# blue_lora_v2.net
KiCad netlist of a schematic drawn in EAGLE
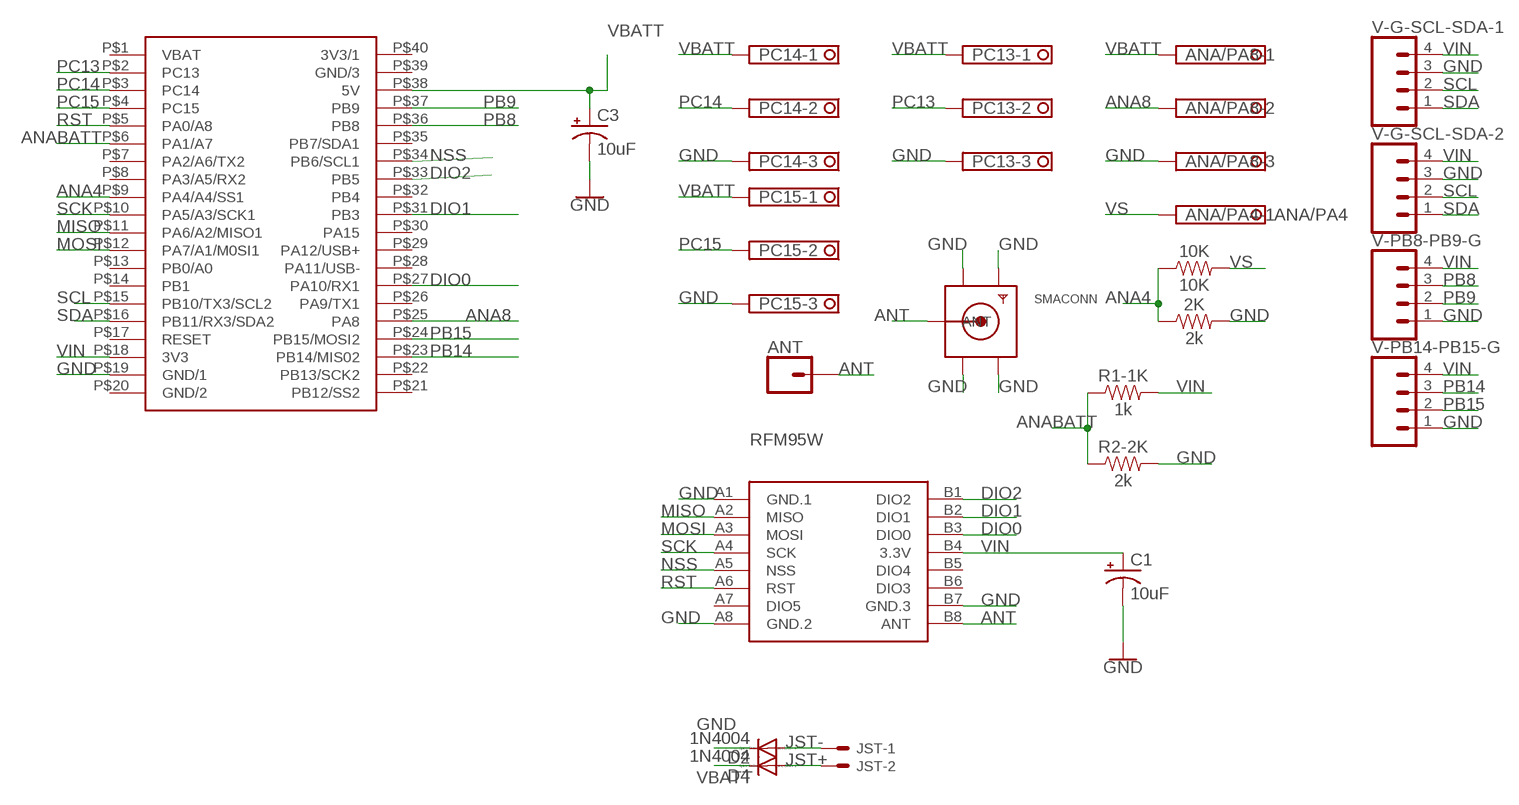
[diagram p0: schematic, sheet 1]

(export (version "E")
  (design (tool "Eeschema 10.0.6"))
  (components
    (comp (ref "2K")
      (value "2k")
      (footprint "eagle-import:AXIAL-0.3-KIT")
      (libsource (lib "eagle-import") (part "1KOHM-HORIZ_KIT-1/4W-1%"))
    )
    (comp (ref "10K")
      (value "10K")
      (footprint "eagle-import:AXIAL-0.3-KIT")
      (libsource (lib "eagle-import") (part "1KOHM-HORIZ_KIT-1/4W-1%"))
    )
    (comp (ref "ANA/PA4")
      (value "ANA/PA4")
      (footprint "eagle-import:TERMINAL-BLOCK-2-PIN-3.5MM-LONG-PAD")
      (libsource (lib "eagle-import") (part "TERMINAL-BLOCK-3.5MM-2-PIN-LONG-PAD"))
    )
    (comp (ref "ANA/PA8")
      (value "TERMINAL-BLOCK-3.5MM-3-PIN-LONG-PAD")
      (footprint "eagle-import:TERMINAL-BLOCK-3-PIN-3.5MM-LONG-PAD")
      (libsource (lib "eagle-import") (part "TERMINAL-BLOCK-3.5MM-3-PIN-LONG-PAD"))
    )
    (comp (ref "ANT")
      (value "CONN_01")
      (footprint "eagle-import:1X01")
      (libsource (lib "eagle-import") (part "CONN_01"))
    )
    (comp (ref "C1")
      (value "10uF")
      (footprint "eagle-import:CPOL-RADIAL-2.5MM-5MM")
      (libsource (lib "eagle-import") (part "10UF-POLAR-RADIAL-2.5MM-25V-20%"))
    )
    (comp (ref "C3")
      (value "10uF")
      (footprint "eagle-import:CPOL-RADIAL-2.5MM-5MM")
      (libsource (lib "eagle-import") (part "10UF-POLAR-RADIAL-2.5MM-25V-20%"))
    )
    (comp (ref "D2")
      (value "1N4004")
      (footprint "eagle-import:DO41-10")
      (libsource (lib "eagle-import") (part "1N4004"))
    )
    (comp (ref "D4")
      (value "1N4004")
      (footprint "eagle-import:DO41-10")
      (libsource (lib "eagle-import") (part "1N4004"))
    )
    (comp (ref "JST")
      (value "JST-XH-02-PIN-LONG-PAD")
      (footprint "eagle-import:JST-XH-02-PACKAGE-LONG-PAD")
      (libsource (lib "eagle-import") (part "JST-XH-02-PIN-LONG-PAD"))
    )
    (comp (ref "PC13")
      (value "TERMINAL-BLOCK-3.5MM-3-PIN-LONG-PAD")
      (footprint "eagle-import:TERMINAL-BLOCK-3-PIN-3.5MM-LONG-PAD")
      (libsource (lib "eagle-import") (part "TERMINAL-BLOCK-3.5MM-3-PIN-LONG-PAD"))
    )
    (comp (ref "PC14")
      (value "TERMINAL-BLOCK-3.5MM-3-PIN-LONG-PAD")
      (footprint "eagle-import:TERMINAL-BLOCK-3-PIN-3.5MM-LONG-PAD")
      (libsource (lib "eagle-import") (part "TERMINAL-BLOCK-3.5MM-3-PIN-LONG-PAD"))
    )
    (comp (ref "PC15")
      (value "TERMINAL-BLOCK-3.5MM-3-PIN-LONG-PAD")
      (footprint "eagle-import:TERMINAL-BLOCK-3-PIN-3.5MM-LONG-PAD")
      (libsource (lib "eagle-import") (part "TERMINAL-BLOCK-3.5MM-3-PIN-LONG-PAD"))
    )
    (comp (ref "R1-1K")
      (value "1k")
      (footprint "eagle-import:AXIAL-0.3-KIT")
      (libsource (lib "eagle-import") (part "1KOHM-HORIZ_KIT-1/4W-1%"))
    )
    (comp (ref "R2-2K")
      (value "2k")
      (footprint "eagle-import:AXIAL-0.3-KIT")
      (libsource (lib "eagle-import") (part "1KOHM-HORIZ_KIT-1/4W-1%"))
    )
    (comp (ref "RFM95W")
      (value "WIRELESS-LORA-RFM95W#SMD")
      (footprint "eagle-import:WIRELESS-LORA-RFM95W#SMD")
      (libsource (lib "eagle-import") (part "WIRELESS-LORA-RFM95W#SMD"))
    )
    (comp (ref "SMACONN")
      (value "SMACONNECTOR_EDGE")
      (footprint "eagle-import:SMA_EDGELAUNCH")
      (libsource (lib "eagle-import") (part "SMACONNECTOR_EDGE"))
    )
    (comp (ref "U$2")
      (value "BLUEPILL")
      (footprint "eagle-import:BLUEPILL")
      (libsource (lib "eagle-import") (part "BLUEPILL"))
    )
    (comp (ref "V-G-SCL-SDA-1")
      (value "CONN_04LOCK_LONGPADS")
      (footprint "eagle-import:1X04_LOCK_LONGPADS")
      (libsource (lib "eagle-import") (part "CONN_04LOCK_LONGPADS"))
    )
    (comp (ref "V-G-SCL-SDA-2")
      (value "CONN_04LOCK_LONGPADS")
      (footprint "eagle-import:1X04_LOCK_LONGPADS")
      (libsource (lib "eagle-import") (part "CONN_04LOCK_LONGPADS"))
    )
    (comp (ref "V-PB8-PB9-G")
      (value "CONN_04LOCK_LONGPADS")
      (footprint "eagle-import:1X04_LOCK_LONGPADS")
      (libsource (lib "eagle-import") (part "CONN_04LOCK_LONGPADS"))
    )
    (comp (ref "V-PB14-PB15-G")
      (value "CONN_04LOCK_LONGPADS")
      (footprint "eagle-import:1X04_LOCK_LONGPADS")
      (libsource (lib "eagle-import") (part "CONN_04LOCK_LONGPADS"))
    )
  )
  (nets
    (net (code "1") (name "/ANA4") (class "Default")
      (node (ref "10K") (pin "P$1") (pinfunction "1_P$1") (pintype "passive"))
      (node (ref "2K") (pin "P$1") (pinfunction "1_P$1") (pintype "passive"))
      (node (ref "U$2") (pin "P$9") (pinfunction "PA4/A4/SS1_P$9") (pintype "bidirectional"))
    )
    (net (code "2") (name "/ANA8") (class "Default")
      (node (ref "ANA/PA8") (pin "2") (pinfunction "K_2") (pintype "passive"))
      (node (ref "U$2") (pin "P$25") (pinfunction "PA8_P$25") (pintype "bidirectional"))
    )
    (net (code "3") (name "/ANABATT") (class "Default")
      (node (ref "R1-1K") (pin "P$1") (pinfunction "1_P$1") (pintype "passive"))
      (node (ref "R2-2K") (pin "P$1") (pinfunction "1_P$1") (pintype "passive"))
      (node (ref "U$2") (pin "P$6") (pinfunction "PA1/A7_P$6") (pintype "bidirectional"))
    )
    (net (code "4") (name "/ANT") (class "Default")
      (node (ref "ANT") (pin "1") (pinfunction "1_1") (pintype "passive"))
      (node (ref "RFM95W") (pin "B8") (pinfunction "ANT_B8") (pintype "passive"))
      (node (ref "SMACONN") (pin "P") (pinfunction "ANT_P") (pintype "bidirectional"))
    )
    (net (code "5") (name "/DIO0") (class "Default")
      (node (ref "RFM95W") (pin "B3") (pinfunction "DIO0_B3") (pintype "bidirectional"))
      (node (ref "U$2") (pin "P$27") (pinfunction "PA10/RX1_P$27") (pintype "bidirectional"))
    )
    (net (code "6") (name "/DIO1") (class "Default")
      (node (ref "RFM95W") (pin "B2") (pinfunction "DIO1_B2") (pintype "bidirectional"))
      (node (ref "U$2") (pin "P$31") (pinfunction "PB3_P$31") (pintype "bidirectional"))
    )
    (net (code "7") (name "/DIO2") (class "Default")
      (node (ref "RFM95W") (pin "B1") (pinfunction "DIO2_B1") (pintype "bidirectional"))
      (node (ref "U$2") (pin "P$33") (pinfunction "PB5_P$33") (pintype "bidirectional"))
    )
    (net (code "8") (name "/JST+") (class "Default")
      (node (ref "D4") (pin "A") (pinfunction "A_A") (pintype "passive"))
      (node (ref "JST") (pin "2") (pinfunction "S_2") (pintype "passive"))
    )
    (net (code "9") (name "/JST-") (class "Default")
      (node (ref "D2") (pin "A") (pinfunction "A_A") (pintype "passive"))
      (node (ref "JST") (pin "1") (pinfunction "S_1") (pintype "passive"))
    )
    (net (code "10") (name "/MISO") (class "Default")
      (node (ref "RFM95W") (pin "A2") (pinfunction "MISO_A2") (pintype "bidirectional"))
      (node (ref "U$2") (pin "P$11") (pinfunction "PA6/A2/MISO1_P$11") (pintype "bidirectional"))
    )
    (net (code "11") (name "/MOSI") (class "Default")
      (node (ref "RFM95W") (pin "A3") (pinfunction "MOSI_A3") (pintype "bidirectional"))
      (node (ref "U$2") (pin "P$12") (pinfunction "PA7/A1/M0SI1_P$12") (pintype "bidirectional"))
    )
    (net (code "12") (name "/NSS") (class "Default")
      (node (ref "RFM95W") (pin "A5") (pinfunction "NSS_A5") (pintype "bidirectional"))
      (node (ref "U$2") (pin "P$34") (pinfunction "PB6/SCL1_P$34") (pintype "bidirectional"))
    )
    (net (code "13") (name "/PB8") (class "Default")
      (node (ref "U$2") (pin "P$36") (pinfunction "PB8_P$36") (pintype "bidirectional"))
      (node (ref "V-PB8-PB9-G") (pin "3") (pinfunction "3_3") (pintype "passive"))
    )
    (net (code "14") (name "/PB9") (class "Default")
      (node (ref "U$2") (pin "P$37") (pinfunction "PB9_P$37") (pintype "bidirectional"))
      (node (ref "V-PB8-PB9-G") (pin "2") (pinfunction "2_2") (pintype "passive"))
    )
    (net (code "15") (name "/PB14") (class "Default")
      (node (ref "U$2") (pin "P$23") (pinfunction "PB14/MIS02_P$23") (pintype "bidirectional"))
      (node (ref "V-PB14-PB15-G") (pin "3") (pinfunction "3_3") (pintype "passive"))
    )
    (net (code "16") (name "/PB15") (class "Default")
      (node (ref "U$2") (pin "P$24") (pinfunction "PB15/MOSI2_P$24") (pintype "bidirectional"))
      (node (ref "V-PB14-PB15-G") (pin "2") (pinfunction "2_2") (pintype "passive"))
    )
    (net (code "17") (name "/PC13") (class "Default")
      (node (ref "PC13") (pin "2") (pinfunction "K_2") (pintype "passive"))
      (node (ref "U$2") (pin "P$2") (pinfunction "PC13_P$2") (pintype "bidirectional"))
    )
    (net (code "18") (name "/PC14") (class "Default")
      (node (ref "PC14") (pin "2") (pinfunction "K_2") (pintype "passive"))
      (node (ref "U$2") (pin "P$3") (pinfunction "PC14_P$3") (pintype "bidirectional"))
    )
    (net (code "19") (name "/PC15") (class "Default")
      (node (ref "PC15") (pin "2") (pinfunction "K_2") (pintype "passive"))
      (node (ref "U$2") (pin "P$4") (pinfunction "PC15_P$4") (pintype "bidirectional"))
    )
    (net (code "20") (name "/RST") (class "Default")
      (node (ref "RFM95W") (pin "A6") (pinfunction "RST_A6") (pintype "bidirectional"))
      (node (ref "U$2") (pin "P$5") (pinfunction "PA0/A8_P$5") (pintype "bidirectional"))
    )
    (net (code "21") (name "/SCK") (class "Default")
      (node (ref "RFM95W") (pin "A4") (pinfunction "SCK_A4") (pintype "bidirectional"))
      (node (ref "U$2") (pin "P$10") (pinfunction "PA5/A3/SCK1_P$10") (pintype "bidirectional"))
    )
    (net (code "22") (name "/SCL") (class "Default")
      (node (ref "U$2") (pin "P$15") (pinfunction "PB10/TX3/SCL2_P$15") (pintype "bidirectional"))
      (node (ref "V-G-SCL-SDA-1") (pin "2") (pinfunction "2_2") (pintype "passive"))
      (node (ref "V-G-SCL-SDA-2") (pin "2") (pinfunction "2_2") (pintype "passive"))
    )
    (net (code "23") (name "/SDA") (class "Default")
      (node (ref "U$2") (pin "P$16") (pinfunction "PB11/RX3/SDA2_P$16") (pintype "bidirectional"))
      (node (ref "V-G-SCL-SDA-1") (pin "1") (pinfunction "1_1") (pintype "passive"))
      (node (ref "V-G-SCL-SDA-2") (pin "1") (pinfunction "1_1") (pintype "passive"))
    )
    (net (code "24") (name "/VBATT") (class "Default")
      (node (ref "ANA/PA8") (pin "1") (pinfunction "K_1") (pintype "passive"))
      (node (ref "C3") (pin "1") (pinfunction "+_1") (pintype "passive"))
      (node (ref "D4") (pin "C") (pinfunction "C_C") (pintype "passive"))
      (node (ref "PC13") (pin "1") (pinfunction "K_1") (pintype "passive"))
      (node (ref "PC14") (pin "1") (pinfunction "K_1") (pintype "passive"))
      (node (ref "PC15") (pin "1") (pinfunction "K_1") (pintype "passive"))
      (node (ref "U$2") (pin "P$38") (pinfunction "5V_P$38") (pintype "bidirectional"))
    )
    (net (code "25") (name "/VIN") (class "Default")
      (node (ref "C1") (pin "1") (pinfunction "+_1") (pintype "passive"))
      (node (ref "R1-1K") (pin "P$2") (pinfunction "2_P$2") (pintype "passive"))
      (node (ref "RFM95W") (pin "B4") (pinfunction "3.3V_B4") (pintype "power_in"))
      (node (ref "U$2") (pin "P$18") (pinfunction "3V3_P$18") (pintype "bidirectional"))
      (node (ref "V-G-SCL-SDA-1") (pin "4") (pinfunction "4_4") (pintype "passive"))
      (node (ref "V-G-SCL-SDA-2") (pin "4") (pinfunction "4_4") (pintype "passive"))
      (node (ref "V-PB14-PB15-G") (pin "4") (pinfunction "4_4") (pintype "passive"))
      (node (ref "V-PB8-PB9-G") (pin "4") (pinfunction "4_4") (pintype "passive"))
    )
    (net (code "26") (name "/VS") (class "Default")
      (node (ref "10K") (pin "P$2") (pinfunction "2_P$2") (pintype "passive"))
      (node (ref "ANA/PA4") (pin "1") (pinfunction "K_1") (pintype "passive"))
    )
    (net (code "27") (name "GND") (class "Default")
      (node (ref "2K") (pin "P$2") (pinfunction "2_P$2") (pintype "passive"))
      (node (ref "ANA/PA8") (pin "3") (pinfunction "K_3") (pintype "passive"))
      (node (ref "C1") (pin "2") (pinfunction "-_2") (pintype "passive"))
      (node (ref "C3") (pin "2") (pinfunction "-_2") (pintype "passive"))
      (node (ref "D2") (pin "C") (pinfunction "C_C") (pintype "passive"))
      (node (ref "PC13") (pin "3") (pinfunction "K_3") (pintype "passive"))
      (node (ref "PC14") (pin "3") (pinfunction "K_3") (pintype "passive"))
      (node (ref "PC15") (pin "3") (pinfunction "K_3") (pintype "passive"))
      (node (ref "R2-2K") (pin "P$2") (pinfunction "2_P$2") (pintype "passive"))
      (node (ref "RFM95W") (pin "A1") (pinfunction "GND.1_A1") (pintype "power_in"))
      (node (ref "RFM95W") (pin "A8") (pinfunction "GND.2_A8") (pintype "power_in"))
      (node (ref "RFM95W") (pin "B7") (pinfunction "GND.3_B7") (pintype "power_in"))
      (node (ref "SMACONN") (pin "GND@1") (pinfunction "GND4_GND@1") (pintype "power_in"))
      (node (ref "SMACONN") (pin "GND@2") (pinfunction "GND3_GND@2") (pintype "power_in"))
      (node (ref "SMACONN") (pin "GND@3") (pinfunction "GND2_GND@3") (pintype "power_in"))
      (node (ref "SMACONN") (pin "GND@4") (pinfunction "GND1_GND@4") (pintype "power_in"))
      (node (ref "U$2") (pin "P$19") (pinfunction "GND/1_P$19") (pintype "bidirectional"))
      (node (ref "V-G-SCL-SDA-1") (pin "3") (pinfunction "3_3") (pintype "passive"))
      (node (ref "V-G-SCL-SDA-2") (pin "3") (pinfunction "3_3") (pintype "passive"))
      (node (ref "V-PB14-PB15-G") (pin "1") (pinfunction "1_1") (pintype "passive"))
      (node (ref "V-PB8-PB9-G") (pin "1") (pinfunction "1_1") (pintype "passive"))
    )
    (net (code "28") (name "unconnected-(RFM95W-DIO3-PadB6)") (class "Default")
      (node (ref "RFM95W") (pin "B6") (pinfunction "DIO3_B6") (pintype "bidirectional"))
    )
    (net (code "29") (name "unconnected-(RFM95W-DIO4-PadB5)") (class "Default")
      (node (ref "RFM95W") (pin "B5") (pinfunction "DIO4_B5") (pintype "bidirectional"))
    )
    (net (code "30") (name "unconnected-(RFM95W-DIO5-PadA7)") (class "Default")
      (node (ref "RFM95W") (pin "A7") (pinfunction "DIO5_A7") (pintype "bidirectional"))
    )
    (net (code "31") (name "unconnected-(U$2-3V3{slash}1-PadP$40)") (class "Default")
      (node (ref "U$2") (pin "P$40") (pinfunction "3V3/1_P$40") (pintype "bidirectional"))
    )
    (net (code "32") (name "unconnected-(U$2-GND{slash}2-PadP$20)") (class "Default")
      (node (ref "U$2") (pin "P$20") (pinfunction "GND/2_P$20") (pintype "bidirectional"))
    )
    (net (code "33") (name "unconnected-(U$2-GND{slash}3-PadP$39)") (class "Default")
      (node (ref "U$2") (pin "P$39") (pinfunction "GND/3_P$39") (pintype "bidirectional"))
    )
    (net (code "34") (name "unconnected-(U$2-PA2{slash}A6{slash}TX2-PadP$7)") (class "Default")
      (node (ref "U$2") (pin "P$7") (pinfunction "PA2/A6/TX2_P$7") (pintype "bidirectional"))
    )
    (net (code "35") (name "unconnected-(U$2-PA3{slash}A5{slash}RX2-PadP$8)") (class "Default")
      (node (ref "U$2") (pin "P$8") (pinfunction "PA3/A5/RX2_P$8") (pintype "bidirectional"))
    )
    (net (code "36") (name "unconnected-(U$2-PA9{slash}TX1-PadP$26)") (class "Default")
      (node (ref "U$2") (pin "P$26") (pinfunction "PA9/TX1_P$26") (pintype "bidirectional"))
    )
    (net (code "37") (name "unconnected-(U$2-PA11{slash}USB--PadP$28)") (class "Default")
      (node (ref "U$2") (pin "P$28") (pinfunction "PA11/USB-_P$28") (pintype "bidirectional"))
    )
    (net (code "38") (name "unconnected-(U$2-PA12{slash}USB+-PadP$29)") (class "Default")
      (node (ref "U$2") (pin "P$29") (pinfunction "PA12/USB+_P$29") (pintype "bidirectional"))
    )
    (net (code "39") (name "unconnected-(U$2-PA15-PadP$30)") (class "Default")
      (node (ref "U$2") (pin "P$30") (pinfunction "PA15_P$30") (pintype "bidirectional"))
    )
    (net (code "40") (name "unconnected-(U$2-PB0{slash}A0-PadP$13)") (class "Default")
      (node (ref "U$2") (pin "P$13") (pinfunction "PB0/A0_P$13") (pintype "bidirectional"))
    )
    (net (code "41") (name "unconnected-(U$2-PB1-PadP$14)") (class "Default")
      (node (ref "U$2") (pin "P$14") (pinfunction "PB1_P$14") (pintype "bidirectional"))
    )
    (net (code "42") (name "unconnected-(U$2-PB4-PadP$32)") (class "Default")
      (node (ref "U$2") (pin "P$32") (pinfunction "PB4_P$32") (pintype "bidirectional"))
    )
    (net (code "43") (name "unconnected-(U$2-PB7{slash}SDA1-PadP$35)") (class "Default")
      (node (ref "U$2") (pin "P$35") (pinfunction "PB7/SDA1_P$35") (pintype "bidirectional"))
    )
    (net (code "44") (name "unconnected-(U$2-PB12{slash}SS2-PadP$21)") (class "Default")
      (node (ref "U$2") (pin "P$21") (pinfunction "PB12/SS2_P$21") (pintype "bidirectional"))
    )
    (net (code "45") (name "unconnected-(U$2-PB13{slash}SCK2-PadP$22)") (class "Default")
      (node (ref "U$2") (pin "P$22") (pinfunction "PB13/SCK2_P$22") (pintype "bidirectional"))
    )
    (net (code "46") (name "unconnected-(U$2-RESET-PadP$17)") (class "Default")
      (node (ref "U$2") (pin "P$17") (pinfunction "RESET_P$17") (pintype "bidirectional"))
    )
    (net (code "47") (name "unconnected-(U$2-VBAT-PadP$1)") (class "Default")
      (node (ref "U$2") (pin "P$1") (pinfunction "VBAT_P$1") (pintype "bidirectional"))
    )
  )
)
